# RFM69_BOB.net
KiCad netlist of a schematic drawn in EAGLE
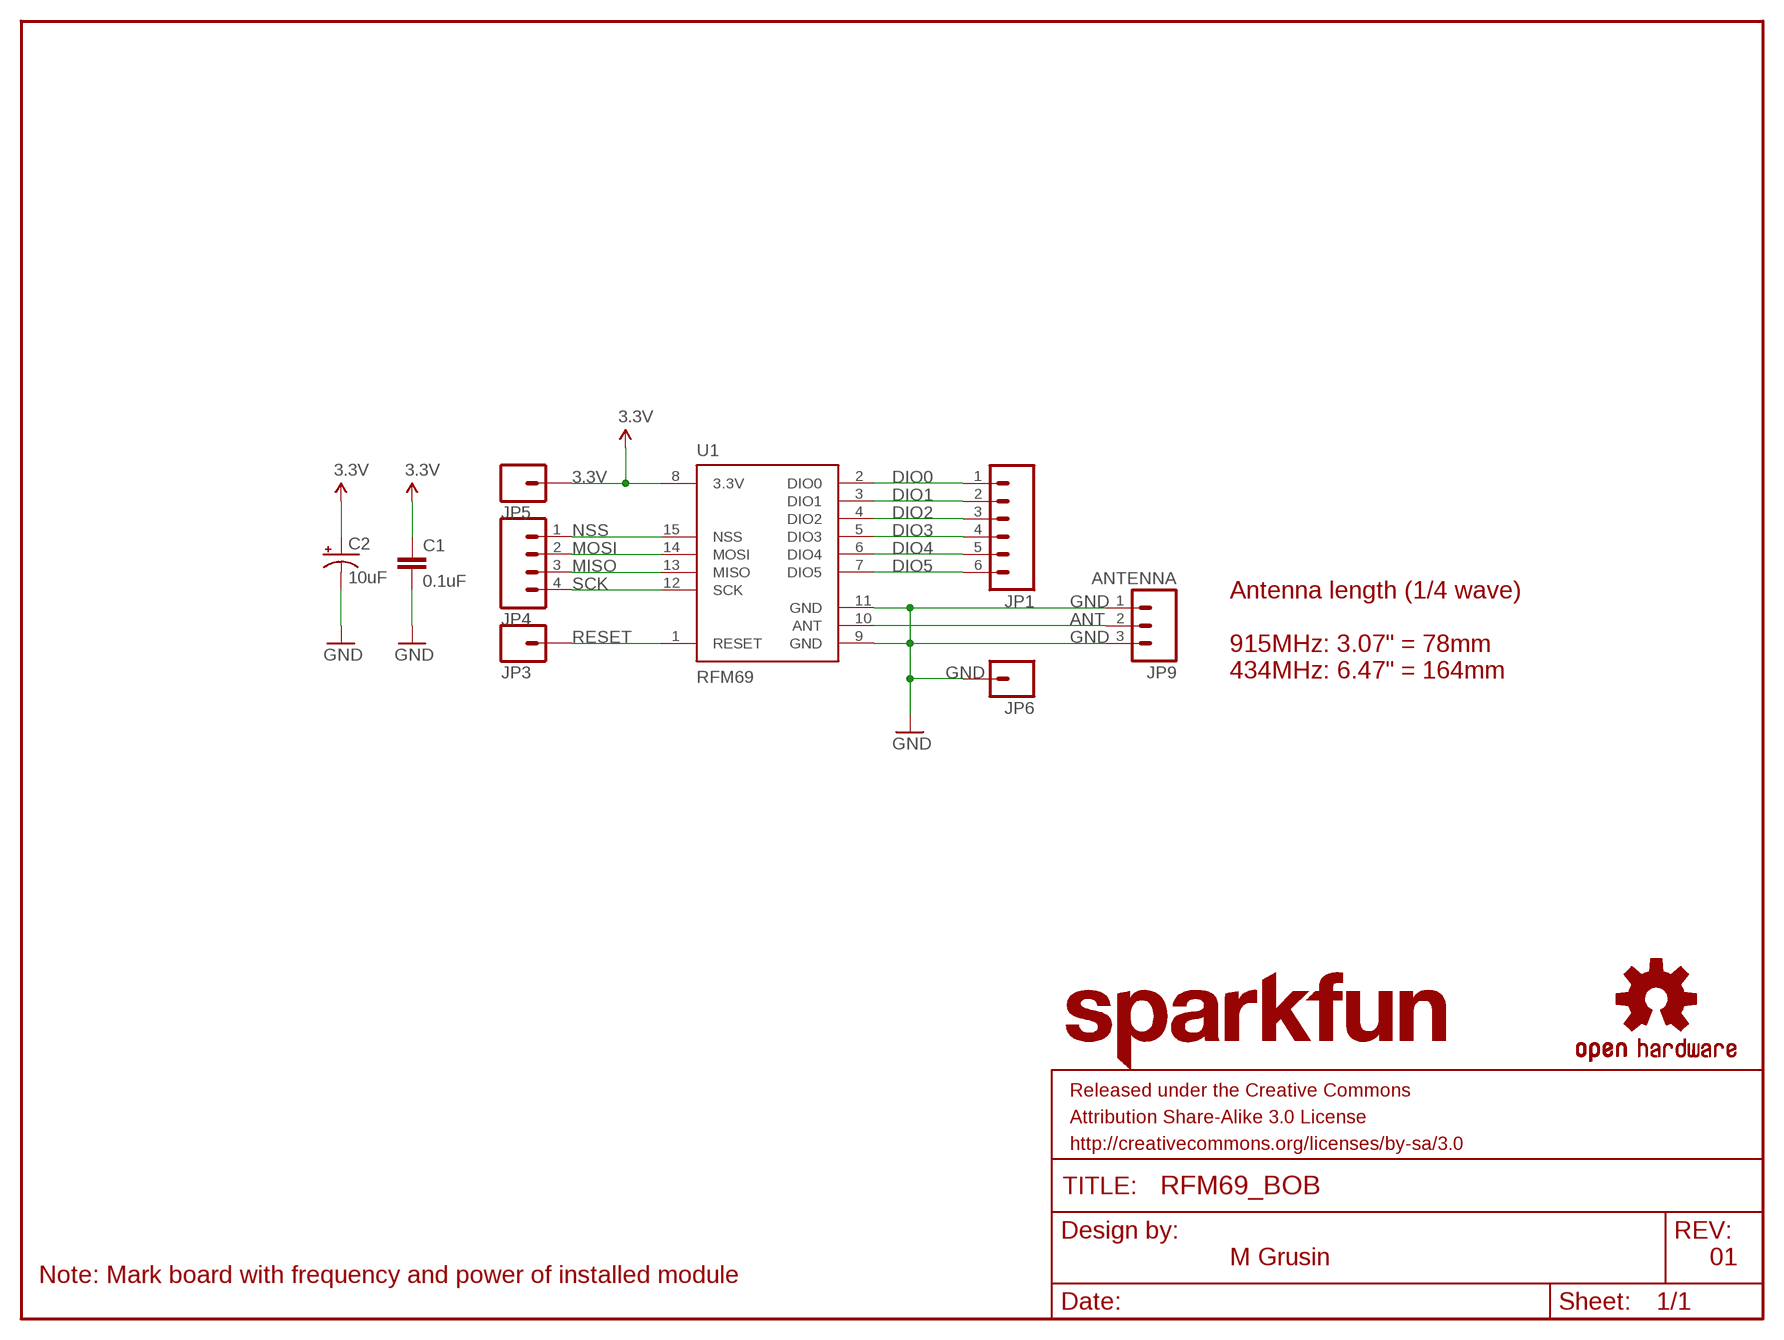
[diagram p0: schematic, sheet 1]

(export (version "E")
  (design (tool "Eeschema 10.0.6"))
  (components
    (comp (ref "C1")
      (value "0.1uF")
      (footprint "eagle-import:0603-CAP")
      (libsource (lib "eagle-import") (part "0.1UF-25V(+80/-20%)(0603)"))
    )
    (comp (ref "C2")
      (value "10uF")
      (footprint "eagle-import:EIA3216")
      (libsource (lib "eagle-import") (part "10UF-16V-10%(TANT)"))
    )
    (comp (ref "FRAME1")
      (value "FRAME-LETTER")
      (footprint "eagle-import:CREATIVE_COMMONS")
      (libsource (lib "eagle-import") (part "FRAME-LETTER"))
    )
    (comp (ref "JP1")
      (value "M06_NOSILK_ROUND")
      (footprint "eagle-import:1X06_NO_SILK_ROUND")
      (libsource (lib "eagle-import") (part "M06_NOSILK_ROUND"))
    )
    (comp (ref "JP3")
      (value "M01SMDNS")
      (footprint "eagle-import:1X01NS")
      (libsource (lib "eagle-import") (part "M01SMDNS"))
    )
    (comp (ref "JP4")
      (value "M041X04_NO_SILK_ROUND")
      (footprint "eagle-import:1X04_NO_SILK_ROUND")
      (libsource (lib "eagle-import") (part "M041X04_NO_SILK_ROUND"))
    )
    (comp (ref "JP5")
      (value "M01SMDNS")
      (footprint "eagle-import:1X01NS")
      (libsource (lib "eagle-import") (part "M01SMDNS"))
    )
    (comp (ref "JP6")
      (value "M01SMDNS")
      (footprint "eagle-import:1X01NS")
      (libsource (lib "eagle-import") (part "M01SMDNS"))
    )
    (comp (ref "JP9")
      (value "ANTENNA")
      (footprint "eagle-import:1X03_ROUND_ONLY_NO_SILK")
      (libsource (lib "eagle-import") (part "M03_ROUND_ONLY_NO_SILK"))
    )
    (comp (ref "LOGO1")
      (value "SFE_LOGO_NAME.1_INCH")
      (footprint "eagle-import:SFE_LOGO_NAME_.1")
      (libsource (lib "eagle-import") (part "SFE_LOGO_NAME.1_INCH"))
    )
    (comp (ref "LOGO2")
      (value "OSHW-LOGOS")
      (footprint "eagle-import:OSHW-LOGO-S")
      (libsource (lib "eagle-import") (part "OSHW-LOGOS"))
    )
    (comp (ref "U1")
      (value "RFM69")
      (footprint "eagle-import:RFM69")
      (libsource (lib "eagle-import") (part "RFM69"))
    )
  )
  (nets
    (net (code "1") (name "/ANT") (class "Default")
      (node (ref "JP9") (pin "2") (pinfunction "2_2") (pintype "passive"))
      (node (ref "U1") (pin "10") (pinfunction "ANT_10") (pintype "bidirectional"))
    )
    (net (code "2") (name "/DIO0") (class "Default")
      (node (ref "JP1") (pin "1") (pinfunction "1_1") (pintype "passive"))
      (node (ref "U1") (pin "2") (pinfunction "DIO0_2") (pintype "bidirectional"))
    )
    (net (code "3") (name "/DIO1") (class "Default")
      (node (ref "JP1") (pin "2") (pinfunction "2_2") (pintype "passive"))
      (node (ref "U1") (pin "3") (pinfunction "DIO1_3") (pintype "bidirectional"))
    )
    (net (code "4") (name "/DIO2") (class "Default")
      (node (ref "JP1") (pin "3") (pinfunction "3_3") (pintype "passive"))
      (node (ref "U1") (pin "4") (pinfunction "DIO2_4") (pintype "bidirectional"))
    )
    (net (code "5") (name "/DIO3") (class "Default")
      (node (ref "JP1") (pin "4") (pinfunction "4_4") (pintype "passive"))
      (node (ref "U1") (pin "5") (pinfunction "DIO3_5") (pintype "bidirectional"))
    )
    (net (code "6") (name "/DIO4") (class "Default")
      (node (ref "JP1") (pin "5") (pinfunction "5_5") (pintype "passive"))
      (node (ref "U1") (pin "6") (pinfunction "DIO4_6") (pintype "bidirectional"))
    )
    (net (code "7") (name "/DIO5") (class "Default")
      (node (ref "JP1") (pin "6") (pinfunction "6_6") (pintype "passive"))
      (node (ref "U1") (pin "7") (pinfunction "DIO5_7") (pintype "bidirectional"))
    )
    (net (code "8") (name "/MISO") (class "Default")
      (node (ref "JP4") (pin "3") (pinfunction "3_3") (pintype "passive"))
      (node (ref "U1") (pin "13") (pinfunction "MISO_13") (pintype "bidirectional"))
    )
    (net (code "9") (name "/MOSI") (class "Default")
      (node (ref "JP4") (pin "2") (pinfunction "2_2") (pintype "passive"))
      (node (ref "U1") (pin "14") (pinfunction "MOSI_14") (pintype "bidirectional"))
    )
    (net (code "10") (name "/NSS") (class "Default")
      (node (ref "JP4") (pin "1") (pinfunction "1_1") (pintype "passive"))
      (node (ref "U1") (pin "15") (pinfunction "NSS_15") (pintype "bidirectional"))
    )
    (net (code "11") (name "/RESET") (class "Default")
      (node (ref "JP3") (pin "1") (pinfunction "1_1") (pintype "passive"))
      (node (ref "U1") (pin "1") (pinfunction "RESET_1") (pintype "bidirectional"))
    )
    (net (code "12") (name "/SCK") (class "Default")
      (node (ref "JP4") (pin "4") (pinfunction "4_4") (pintype "passive"))
      (node (ref "U1") (pin "12") (pinfunction "SCK_12") (pintype "bidirectional"))
    )
    (net (code "13") (name "3.3V") (class "Default")
      (node (ref "C1") (pin "1") (pinfunction "1_1") (pintype "passive"))
      (node (ref "C2") (pin "A") (pinfunction "+_A") (pintype "passive"))
      (node (ref "JP5") (pin "1") (pinfunction "1_1") (pintype "passive"))
      (node (ref "U1") (pin "8") (pinfunction "3.3V_8") (pintype "bidirectional"))
    )
    (net (code "14") (name "GND") (class "Default")
      (node (ref "C1") (pin "2") (pinfunction "2_2") (pintype "passive"))
      (node (ref "C2") (pin "C") (pinfunction "-_C") (pintype "passive"))
      (node (ref "JP6") (pin "1") (pinfunction "1_1") (pintype "passive"))
      (node (ref "JP9") (pin "1") (pinfunction "1_1") (pintype "passive"))
      (node (ref "JP9") (pin "3") (pinfunction "3_3") (pintype "passive"))
      (node (ref "U1") (pin "11") (pinfunction "GND_11") (pintype "bidirectional"))
      (node (ref "U1") (pin "9") (pinfunction "GND_9") (pintype "bidirectional"))
    )
  )
)
